# MCP3221.net
KiCad netlist of a schematic drawn in EAGLE
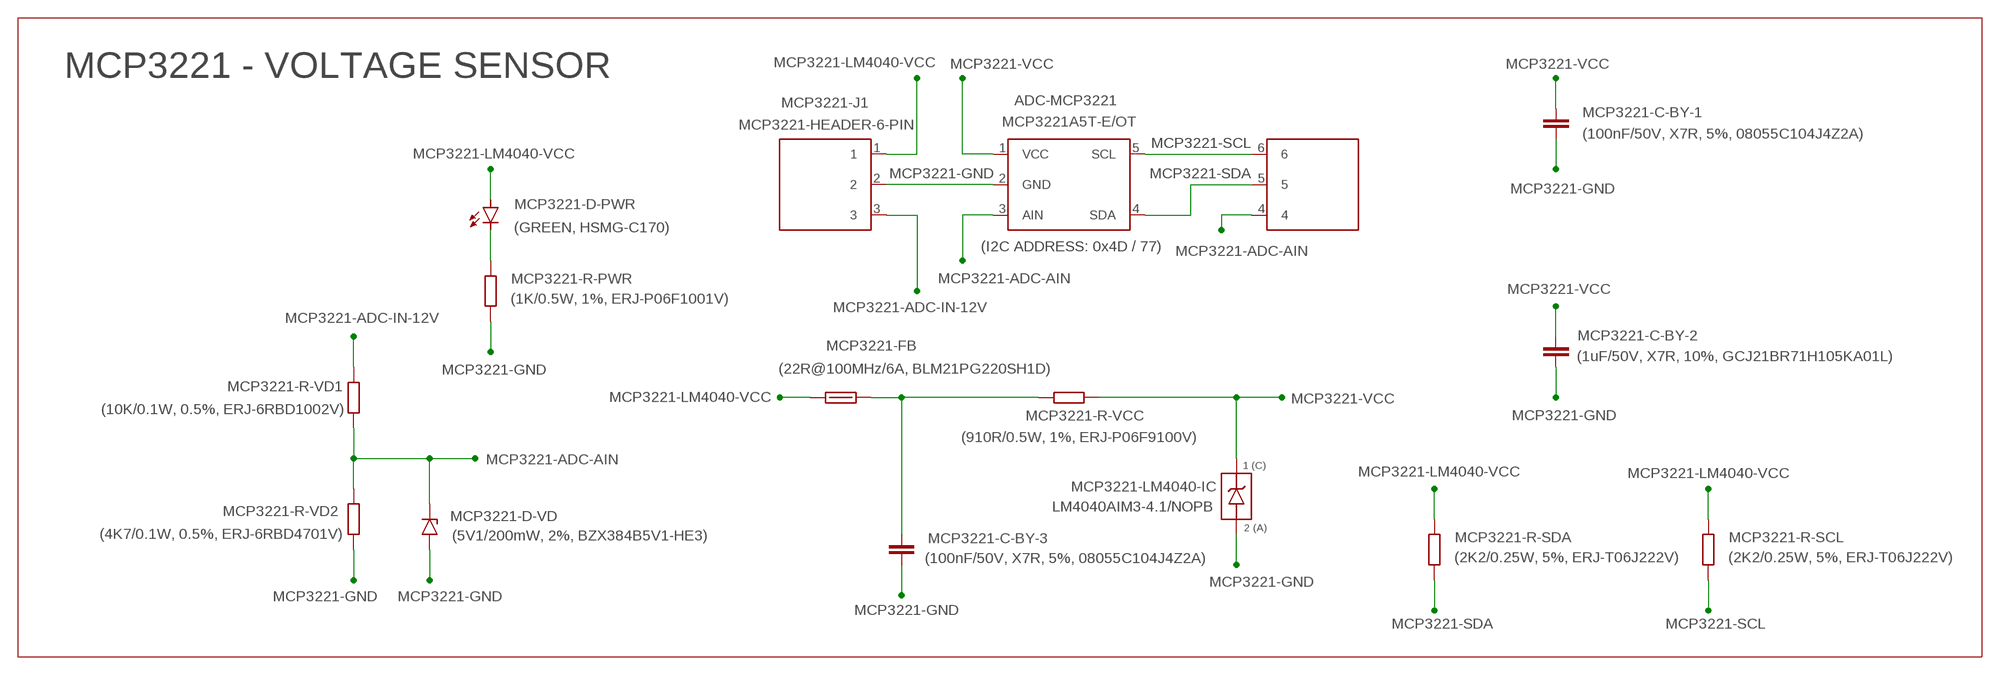
[diagram p0: schematic, sheet 1]

(export (version "E")
  (design (tool "Eeschema 10.0.6"))
  (components
    (comp (ref "ADC-MCP3221")
      (value "MCP3221A5T-E/OT")
      (footprint "eagle-import:SOT-23-5")
      (libsource (lib "eagle-import") (part "MCP3221A5T-E/OT"))
    )
    (comp (ref "MCP3221-C-BY-1")
      (value "(100nF/50V, X7R, 5%, 08055C104J4Z2A)")
      (footprint "eagle-import:0805")
      (libsource (lib "eagle-import") (part "08055C104J4Z2A"))
    )
    (comp (ref "MCP3221-C-BY-2")
      (value "(1uF/50V, X7R, 10%, GCJ21BR71H105KA01L)")
      (footprint "eagle-import:0805")
      (libsource (lib "eagle-import") (part "GCJ21BR71H105KA01L"))
    )
    (comp (ref "MCP3221-C-BY-3")
      (value "(100nF/50V, X7R, 5%, 08055C104J4Z2A)")
      (footprint "eagle-import:0805")
      (libsource (lib "eagle-import") (part "08055C104J4Z2A"))
    )
    (comp (ref "MCP3221-D-PWR")
      (value "(GREEN, HSMG-C170)")
      (footprint "eagle-import:DIODE_0805")
      (libsource (lib "eagle-import") (part "HSMG-C170"))
    )
    (comp (ref "MCP3221-D-VD")
      (value "(5V1/200mW, 2%, BZX384B5V1-HE3)")
      (footprint "eagle-import:SOD-323-DIODE")
      (libsource (lib "eagle-import") (part "BZX384B5V1-HE3"))
    )
    (comp (ref "MCP3221-FB")
      (value "(22R@100MHz/6A, BLM21PG220SH1D)")
      (footprint "eagle-import:0805")
      (libsource (lib "eagle-import") (part "BLM21PG220SH1D"))
    )
    (comp (ref "MCP3221-J1")
      (value "MCP3221-HEADER-6-PIN")
      (footprint "eagle-import:HEADER_2.54MM_6_PIN_VER")
      (libsource (lib "eagle-import") (part "HEADER_6_PIN"))
    )
    (comp (ref "MCP3221-LM4040-IC")
      (value "LM4040AIM3-4.1/NOPB")
      (footprint "eagle-import:SOT-23-3")
      (libsource (lib "eagle-import") (part "LM4040AIM3-4.1/NOPB"))
    )
    (comp (ref "MCP3221-R-PWR")
      (value "(1K/0.5W, 1%, ERJ-P06F1001V)")
      (footprint "eagle-import:0805")
      (libsource (lib "eagle-import") (part "ERJ-P06F1001V"))
    )
    (comp (ref "MCP3221-R-SCL")
      (value "(2K2/0.25W, 5%, ERJ-T06J222V)")
      (footprint "eagle-import:0805")
      (libsource (lib "eagle-import") (part "ERJ-T06J222V"))
    )
    (comp (ref "MCP3221-R-SDA")
      (value "(2K2/0.25W, 5%, ERJ-T06J222V)")
      (footprint "eagle-import:0805")
      (libsource (lib "eagle-import") (part "ERJ-T06J222V"))
    )
    (comp (ref "MCP3221-R-VCC")
      (value "(910R/0.5W, 1%, ERJ-P06F9100V)")
      (footprint "eagle-import:0805")
      (libsource (lib "eagle-import") (part "ERJ-P06F9100V"))
    )
    (comp (ref "MCP3221-R-VD1")
      (value "(10K/0.1W, 0.5%, ERJ-6RBD1002V)")
      (footprint "eagle-import:0805")
      (libsource (lib "eagle-import") (part "ERJ-6RBD1002V"))
    )
    (comp (ref "MCP3221-R-VD2")
      (value "(4K7/0.1W, 0.5%, ERJ-6RBD4701V)")
      (footprint "eagle-import:0805")
      (libsource (lib "eagle-import") (part "ERJ-6RBD4701V"))
    )
  )
  (nets
    (net (code "1") (name "/MCP3221-ADC-AIN") (class "Default")
      (node (ref "ADC-MCP3221") (pin "3") (pinfunction "AIN_3") (pintype "bidirectional"))
      (node (ref "MCP3221-D-VD") (pin "C") (pinfunction "C_C") (pintype "passive"))
      (node (ref "MCP3221-J1") (pin "4") (pinfunction "4_4") (pintype "bidirectional"))
      (node (ref "MCP3221-R-VD1") (pin "2") (pinfunction "2_2") (pintype "passive"))
      (node (ref "MCP3221-R-VD2") (pin "1") (pinfunction "1_1") (pintype "passive"))
    )
    (net (code "2") (name "/MCP3221-ADC-IN-12V") (class "Default")
      (node (ref "MCP3221-J1") (pin "3") (pinfunction "3_3") (pintype "bidirectional"))
      (node (ref "MCP3221-R-VD1") (pin "1") (pinfunction "1_1") (pintype "passive"))
    )
    (net (code "3") (name "/MCP3221-GND") (class "Default")
      (node (ref "ADC-MCP3221") (pin "2") (pinfunction "GND_2") (pintype "power_in"))
      (node (ref "MCP3221-C-BY-1") (pin "2") (pinfunction "C_2") (pintype "passive"))
      (node (ref "MCP3221-C-BY-2") (pin "1") (pinfunction "A_1") (pintype "passive"))
      (node (ref "MCP3221-C-BY-3") (pin "2") (pinfunction "C_2") (pintype "passive"))
      (node (ref "MCP3221-D-VD") (pin "A") (pinfunction "A_A") (pintype "passive"))
      (node (ref "MCP3221-J1") (pin "2") (pinfunction "2_2") (pintype "bidirectional"))
      (node (ref "MCP3221-LM4040-IC") (pin "2") (pinfunction "A_2") (pintype "passive"))
      (node (ref "MCP3221-LM4040-IC") (pin "3") (pinfunction "A_3") (pintype "passive"))
      (node (ref "MCP3221-R-PWR") (pin "1") (pinfunction "1_1") (pintype "passive"))
      (node (ref "MCP3221-R-VD2") (pin "2") (pinfunction "2_2") (pintype "passive"))
    )
    (net (code "4") (name "/MCP3221-LM4040-VCC") (class "Default")
      (node (ref "MCP3221-D-PWR") (pin "A") (pinfunction "A_A") (pintype "passive"))
      (node (ref "MCP3221-FB") (pin "2") (pinfunction "2_2") (pintype "passive"))
      (node (ref "MCP3221-J1") (pin "1") (pinfunction "1_1") (pintype "bidirectional"))
      (node (ref "MCP3221-R-SCL") (pin "2") (pinfunction "2_2") (pintype "passive"))
      (node (ref "MCP3221-R-SDA") (pin "2") (pinfunction "2_2") (pintype "passive"))
    )
    (net (code "5") (name "/MCP3221-SCL") (class "Default")
      (node (ref "ADC-MCP3221") (pin "5") (pinfunction "SCL_5") (pintype "bidirectional"))
      (node (ref "MCP3221-J1") (pin "6") (pinfunction "6_6") (pintype "bidirectional"))
      (node (ref "MCP3221-R-SCL") (pin "1") (pinfunction "1_1") (pintype "passive"))
    )
    (net (code "6") (name "/MCP3221-SDA") (class "Default")
      (node (ref "ADC-MCP3221") (pin "4") (pinfunction "SDA_4") (pintype "bidirectional"))
      (node (ref "MCP3221-J1") (pin "5") (pinfunction "5_5") (pintype "bidirectional"))
      (node (ref "MCP3221-R-SDA") (pin "1") (pinfunction "1_1") (pintype "passive"))
    )
    (net (code "7") (name "/MCP3221-VCC") (class "Default")
      (node (ref "ADC-MCP3221") (pin "1") (pinfunction "VCC_1") (pintype "power_in"))
      (node (ref "MCP3221-C-BY-1") (pin "1") (pinfunction "A_1") (pintype "passive"))
      (node (ref "MCP3221-C-BY-2") (pin "2") (pinfunction "C_2") (pintype "passive"))
      (node (ref "MCP3221-LM4040-IC") (pin "1") (pinfunction "C_1") (pintype "passive"))
      (node (ref "MCP3221-R-VCC") (pin "1") (pinfunction "1_1") (pintype "passive"))
    )
    (net (code "8") (name "Net-(MCP3221-C-BY-3-A)") (class "Default")
      (node (ref "MCP3221-C-BY-3") (pin "1") (pinfunction "A_1") (pintype "passive"))
      (node (ref "MCP3221-FB") (pin "1") (pinfunction "1_1") (pintype "passive"))
      (node (ref "MCP3221-R-VCC") (pin "2") (pinfunction "2_2") (pintype "passive"))
    )
    (net (code "9") (name "Net-(MCP3221-D-PWR-PadC)") (class "Default")
      (node (ref "MCP3221-D-PWR") (pin "C") (pinfunction "C_C") (pintype "passive"))
      (node (ref "MCP3221-R-PWR") (pin "2") (pinfunction "2_2") (pintype "passive"))
    )
  )
)
